# VHDCI_CON.net
KiCad netlist of a schematic drawn in Altium Designer
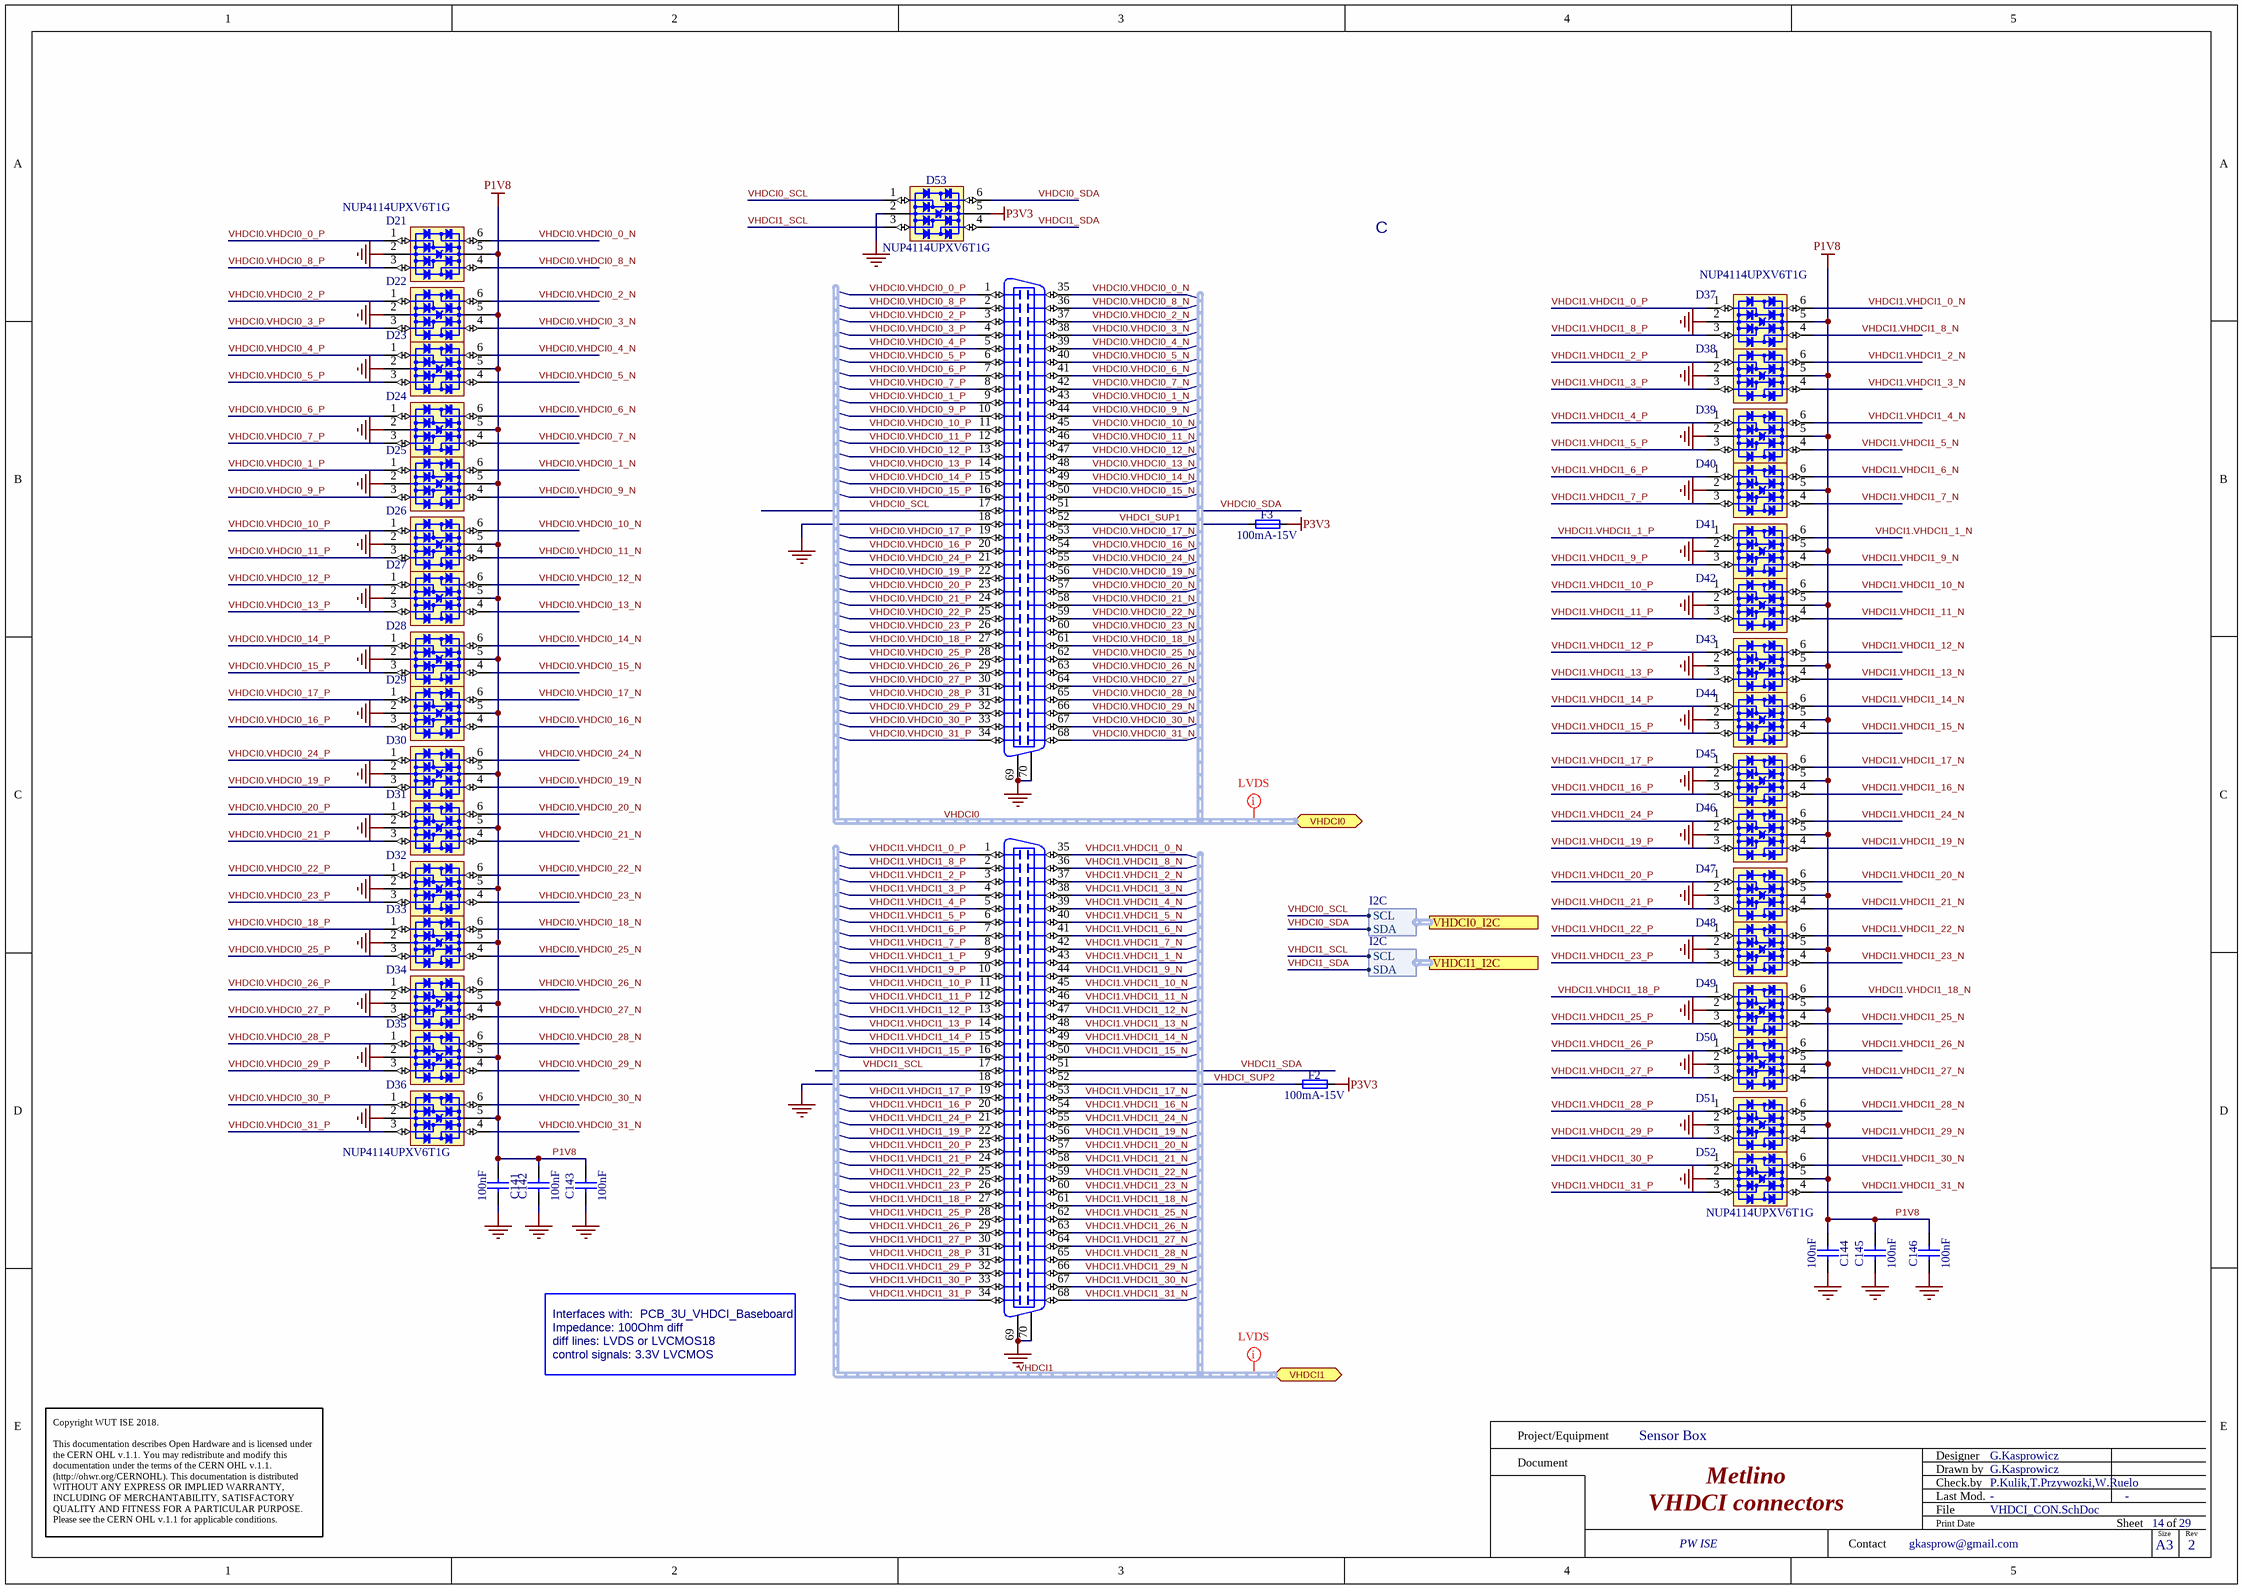
[diagram p0: VHDCI_CON.SchDoc]

(export (version "E")
  (design (tool "Eeschema 10.0.6"))
  (components
    (comp (ref "C141")
      (value "100nF")
      (footprint "CAPC0603X33N")
      (description "Non-polarised capacitor")
      (fields
        (field (name "MANUFACTURER PART NUMBER") "CC0201_100NF_6.3V_10%_X5R")
        (field (name "MANUFACTURER") "GENERIC")
        (field (name "AUTHOR") "CERN DEM JLC")
      )
      (libsource (lib "Capacitors") (part "Capacitor - non polarized"))
    )
    (comp (ref "C142")
      (value "100nF")
      (footprint "CAPC0603X33N")
      (description "Non-polarised capacitor")
      (fields
        (field (name "MANUFACTURER PART NUMBER") "CC0201_100NF_6.3V_10%_X5R")
        (field (name "MANUFACTURER") "GENERIC")
        (field (name "AUTHOR") "CERN DEM JLC")
      )
      (libsource (lib "Capacitors") (part "Capacitor - non polarized"))
    )
    (comp (ref "C143")
      (value "100nF")
      (footprint "CAPC0603X33N")
      (description "Non-polarised capacitor")
      (fields
        (field (name "MANUFACTURER PART NUMBER") "CC0201_100NF_6.3V_10%_X5R")
        (field (name "MANUFACTURER") "GENERIC")
        (field (name "AUTHOR") "CERN DEM JLC")
      )
      (libsource (lib "Capacitors") (part "Capacitor - non polarized"))
    )
    (comp (ref "C144")
      (value "100nF")
      (footprint "CAPC0603X33N")
      (description "Non-polarised capacitor")
      (fields
        (field (name "MANUFACTURER PART NUMBER") "CC0201_100NF_6.3V_10%_X5R")
        (field (name "MANUFACTURER") "GENERIC")
        (field (name "AUTHOR") "CERN DEM JLC")
      )
      (libsource (lib "Capacitors") (part "Capacitor - non polarized"))
    )
    (comp (ref "C145")
      (value "100nF")
      (footprint "CAPC0603X33N")
      (description "Non-polarised capacitor")
      (fields
        (field (name "MANUFACTURER PART NUMBER") "CC0201_100NF_6.3V_10%_X5R")
        (field (name "MANUFACTURER") "GENERIC")
        (field (name "AUTHOR") "CERN DEM JLC")
      )
      (libsource (lib "Capacitors") (part "Capacitor - non polarized"))
    )
    (comp (ref "C146")
      (value "100nF")
      (footprint "CAPC0603X33N")
      (description "Non-polarised capacitor")
      (fields
        (field (name "MANUFACTURER PART NUMBER") "CC0201_100NF_6.3V_10%_X5R")
        (field (name "MANUFACTURER") "GENERIC")
        (field (name "AUTHOR") "CERN DEM JLC")
      )
      (libsource (lib "Capacitors") (part "Capacitor - non polarized"))
    )
    (comp (ref "D21")
      (value "NUP4114UPXV6T1G")
      (footprint "SOTFL50P160X60-6N")
      (fields
        (field (name "MANUFACTURER") "ON SEMICONDUCTOR")
        (field (name "VOLTAGE") "5.5V")
        (field (name "AUTHOR") "CERN DEM JLC")
      )
      (libsource (lib "ICs And Semiconductors") (part "NUP4114"))
    )
    (comp (ref "D22")
      (value "NUP4114UPXV6T1G")
      (footprint "SOTFL50P160X60-6N")
      (fields
        (field (name "MANUFACTURER") "ON SEMICONDUCTOR")
        (field (name "VOLTAGE") "5.5V")
        (field (name "AUTHOR") "CERN DEM JLC")
      )
      (libsource (lib "ICs And Semiconductors") (part "NUP4114"))
    )
    (comp (ref "D23")
      (value "NUP4114UPXV6T1G")
      (footprint "SOTFL50P160X60-6N")
      (fields
        (field (name "MANUFACTURER") "ON SEMICONDUCTOR")
        (field (name "VOLTAGE") "5.5V")
        (field (name "AUTHOR") "CERN DEM JLC")
      )
      (libsource (lib "ICs And Semiconductors") (part "NUP4114"))
    )
    (comp (ref "D24")
      (value "NUP4114UPXV6T1G")
      (footprint "SOTFL50P160X60-6N")
      (fields
        (field (name "MANUFACTURER") "ON SEMICONDUCTOR")
        (field (name "VOLTAGE") "5.5V")
        (field (name "AUTHOR") "CERN DEM JLC")
      )
      (libsource (lib "ICs And Semiconductors") (part "NUP4114"))
    )
    (comp (ref "D25")
      (value "NUP4114UPXV6T1G")
      (footprint "SOTFL50P160X60-6N")
      (fields
        (field (name "MANUFACTURER") "ON SEMICONDUCTOR")
        (field (name "VOLTAGE") "5.5V")
        (field (name "AUTHOR") "CERN DEM JLC")
      )
      (libsource (lib "ICs And Semiconductors") (part "NUP4114"))
    )
    (comp (ref "D26")
      (value "NUP4114UPXV6T1G")
      (footprint "SOTFL50P160X60-6N")
      (fields
        (field (name "MANUFACTURER") "ON SEMICONDUCTOR")
        (field (name "VOLTAGE") "5.5V")
        (field (name "AUTHOR") "CERN DEM JLC")
      )
      (libsource (lib "ICs And Semiconductors") (part "NUP4114"))
    )
    (comp (ref "D27")
      (value "NUP4114UPXV6T1G")
      (footprint "SOTFL50P160X60-6N")
      (fields
        (field (name "MANUFACTURER") "ON SEMICONDUCTOR")
        (field (name "VOLTAGE") "5.5V")
        (field (name "AUTHOR") "CERN DEM JLC")
      )
      (libsource (lib "ICs And Semiconductors") (part "NUP4114"))
    )
    (comp (ref "D28")
      (value "NUP4114UPXV6T1G")
      (footprint "SOTFL50P160X60-6N")
      (fields
        (field (name "MANUFACTURER") "ON SEMICONDUCTOR")
        (field (name "VOLTAGE") "5.5V")
        (field (name "AUTHOR") "CERN DEM JLC")
      )
      (libsource (lib "ICs And Semiconductors") (part "NUP4114"))
    )
    (comp (ref "D29")
      (value "NUP4114UPXV6T1G")
      (footprint "SOTFL50P160X60-6N")
      (fields
        (field (name "MANUFACTURER") "ON SEMICONDUCTOR")
        (field (name "VOLTAGE") "5.5V")
        (field (name "AUTHOR") "CERN DEM JLC")
      )
      (libsource (lib "ICs And Semiconductors") (part "NUP4114"))
    )
    (comp (ref "D30")
      (value "NUP4114UPXV6T1G")
      (footprint "SOTFL50P160X60-6N")
      (fields
        (field (name "MANUFACTURER") "ON SEMICONDUCTOR")
        (field (name "VOLTAGE") "5.5V")
        (field (name "AUTHOR") "CERN DEM JLC")
      )
      (libsource (lib "ICs And Semiconductors") (part "NUP4114"))
    )
    (comp (ref "D31")
      (value "NUP4114UPXV6T1G")
      (footprint "SOTFL50P160X60-6N")
      (fields
        (field (name "MANUFACTURER") "ON SEMICONDUCTOR")
        (field (name "VOLTAGE") "5.5V")
        (field (name "AUTHOR") "CERN DEM JLC")
      )
      (libsource (lib "ICs And Semiconductors") (part "NUP4114"))
    )
    (comp (ref "D32")
      (value "NUP4114UPXV6T1G")
      (footprint "SOTFL50P160X60-6N")
      (fields
        (field (name "MANUFACTURER") "ON SEMICONDUCTOR")
        (field (name "VOLTAGE") "5.5V")
        (field (name "AUTHOR") "CERN DEM JLC")
      )
      (libsource (lib "ICs And Semiconductors") (part "NUP4114"))
    )
    (comp (ref "D33")
      (value "NUP4114UPXV6T1G")
      (footprint "SOTFL50P160X60-6N")
      (fields
        (field (name "MANUFACTURER") "ON SEMICONDUCTOR")
        (field (name "VOLTAGE") "5.5V")
        (field (name "AUTHOR") "CERN DEM JLC")
      )
      (libsource (lib "ICs And Semiconductors") (part "NUP4114"))
    )
    (comp (ref "D34")
      (value "NUP4114UPXV6T1G")
      (footprint "SOTFL50P160X60-6N")
      (fields
        (field (name "MANUFACTURER") "ON SEMICONDUCTOR")
        (field (name "VOLTAGE") "5.5V")
        (field (name "AUTHOR") "CERN DEM JLC")
      )
      (libsource (lib "ICs And Semiconductors") (part "NUP4114"))
    )
    (comp (ref "D35")
      (value "NUP4114UPXV6T1G")
      (footprint "SOTFL50P160X60-6N")
      (fields
        (field (name "MANUFACTURER") "ON SEMICONDUCTOR")
        (field (name "VOLTAGE") "5.5V")
        (field (name "AUTHOR") "CERN DEM JLC")
      )
      (libsource (lib "ICs And Semiconductors") (part "NUP4114"))
    )
    (comp (ref "D36")
      (value "NUP4114UPXV6T1G")
      (footprint "SOTFL50P160X60-6N")
      (fields
        (field (name "MANUFACTURER") "ON SEMICONDUCTOR")
        (field (name "VOLTAGE") "5.5V")
        (field (name "AUTHOR") "CERN DEM JLC")
      )
      (libsource (lib "ICs And Semiconductors") (part "NUP4114"))
    )
    (comp (ref "D37")
      (value "NUP4114UPXV6T1G")
      (footprint "SOTFL50P160X60-6N")
      (fields
        (field (name "MANUFACTURER") "ON SEMICONDUCTOR")
        (field (name "VOLTAGE") "5.5V")
        (field (name "AUTHOR") "CERN DEM JLC")
      )
      (libsource (lib "ICs And Semiconductors") (part "NUP4114"))
    )
    (comp (ref "D38")
      (value "NUP4114UPXV6T1G")
      (footprint "SOTFL50P160X60-6N")
      (fields
        (field (name "MANUFACTURER") "ON SEMICONDUCTOR")
        (field (name "VOLTAGE") "5.5V")
        (field (name "AUTHOR") "CERN DEM JLC")
      )
      (libsource (lib "ICs And Semiconductors") (part "NUP4114"))
    )
    (comp (ref "D39")
      (value "NUP4114UPXV6T1G")
      (footprint "SOTFL50P160X60-6N")
      (fields
        (field (name "MANUFACTURER") "ON SEMICONDUCTOR")
        (field (name "VOLTAGE") "5.5V")
        (field (name "AUTHOR") "CERN DEM JLC")
      )
      (libsource (lib "ICs And Semiconductors") (part "NUP4114"))
    )
    (comp (ref "D40")
      (value "NUP4114UPXV6T1G")
      (footprint "SOTFL50P160X60-6N")
      (fields
        (field (name "MANUFACTURER") "ON SEMICONDUCTOR")
        (field (name "VOLTAGE") "5.5V")
        (field (name "AUTHOR") "CERN DEM JLC")
      )
      (libsource (lib "ICs And Semiconductors") (part "NUP4114"))
    )
    (comp (ref "D41")
      (value "NUP4114UPXV6T1G")
      (footprint "SOTFL50P160X60-6N")
      (fields
        (field (name "MANUFACTURER") "ON SEMICONDUCTOR")
        (field (name "VOLTAGE") "5.5V")
        (field (name "AUTHOR") "CERN DEM JLC")
      )
      (libsource (lib "ICs And Semiconductors") (part "NUP4114"))
    )
    (comp (ref "D42")
      (value "NUP4114UPXV6T1G")
      (footprint "SOTFL50P160X60-6N")
      (fields
        (field (name "MANUFACTURER") "ON SEMICONDUCTOR")
        (field (name "VOLTAGE") "5.5V")
        (field (name "AUTHOR") "CERN DEM JLC")
      )
      (libsource (lib "ICs And Semiconductors") (part "NUP4114"))
    )
    (comp (ref "D43")
      (value "NUP4114UPXV6T1G")
      (footprint "SOTFL50P160X60-6N")
      (fields
        (field (name "MANUFACTURER") "ON SEMICONDUCTOR")
        (field (name "VOLTAGE") "5.5V")
        (field (name "AUTHOR") "CERN DEM JLC")
      )
      (libsource (lib "ICs And Semiconductors") (part "NUP4114"))
    )
    (comp (ref "D44")
      (value "NUP4114UPXV6T1G")
      (footprint "SOTFL50P160X60-6N")
      (fields
        (field (name "MANUFACTURER") "ON SEMICONDUCTOR")
        (field (name "VOLTAGE") "5.5V")
        (field (name "AUTHOR") "CERN DEM JLC")
      )
      (libsource (lib "ICs And Semiconductors") (part "NUP4114"))
    )
    (comp (ref "D45")
      (value "NUP4114UPXV6T1G")
      (footprint "SOTFL50P160X60-6N")
      (fields
        (field (name "MANUFACTURER") "ON SEMICONDUCTOR")
        (field (name "VOLTAGE") "5.5V")
        (field (name "AUTHOR") "CERN DEM JLC")
      )
      (libsource (lib "ICs And Semiconductors") (part "NUP4114"))
    )
    (comp (ref "D46")
      (value "NUP4114UPXV6T1G")
      (footprint "SOTFL50P160X60-6N")
      (fields
        (field (name "MANUFACTURER") "ON SEMICONDUCTOR")
        (field (name "VOLTAGE") "5.5V")
        (field (name "AUTHOR") "CERN DEM JLC")
      )
      (libsource (lib "ICs And Semiconductors") (part "NUP4114"))
    )
    (comp (ref "D47")
      (value "NUP4114UPXV6T1G")
      (footprint "SOTFL50P160X60-6N")
      (fields
        (field (name "MANUFACTURER") "ON SEMICONDUCTOR")
        (field (name "VOLTAGE") "5.5V")
        (field (name "AUTHOR") "CERN DEM JLC")
      )
      (libsource (lib "ICs And Semiconductors") (part "NUP4114"))
    )
    (comp (ref "D48")
      (value "NUP4114UPXV6T1G")
      (footprint "SOTFL50P160X60-6N")
      (fields
        (field (name "MANUFACTURER") "ON SEMICONDUCTOR")
        (field (name "VOLTAGE") "5.5V")
        (field (name "AUTHOR") "CERN DEM JLC")
      )
      (libsource (lib "ICs And Semiconductors") (part "NUP4114"))
    )
    (comp (ref "D49")
      (value "NUP4114UPXV6T1G")
      (footprint "SOTFL50P160X60-6N")
      (fields
        (field (name "MANUFACTURER") "ON SEMICONDUCTOR")
        (field (name "VOLTAGE") "5.5V")
        (field (name "AUTHOR") "CERN DEM JLC")
      )
      (libsource (lib "ICs And Semiconductors") (part "NUP4114"))
    )
    (comp (ref "D50")
      (value "NUP4114UPXV6T1G")
      (footprint "SOTFL50P160X60-6N")
      (fields
        (field (name "MANUFACTURER") "ON SEMICONDUCTOR")
        (field (name "VOLTAGE") "5.5V")
        (field (name "AUTHOR") "CERN DEM JLC")
      )
      (libsource (lib "ICs And Semiconductors") (part "NUP4114"))
    )
    (comp (ref "D51")
      (value "NUP4114UPXV6T1G")
      (footprint "SOTFL50P160X60-6N")
      (fields
        (field (name "MANUFACTURER") "ON SEMICONDUCTOR")
        (field (name "VOLTAGE") "5.5V")
        (field (name "AUTHOR") "CERN DEM JLC")
      )
      (libsource (lib "ICs And Semiconductors") (part "NUP4114"))
    )
    (comp (ref "D52")
      (value "NUP4114UPXV6T1G")
      (footprint "SOTFL50P160X60-6N")
      (fields
        (field (name "MANUFACTURER") "ON SEMICONDUCTOR")
        (field (name "VOLTAGE") "5.5V")
        (field (name "AUTHOR") "CERN DEM JLC")
      )
      (libsource (lib "ICs And Semiconductors") (part "NUP4114"))
    )
    (comp (ref "D53")
      (value "NUP4114UPXV6T1G")
      (footprint "SOTFL50P160X60-6N")
      (fields
        (field (name "MANUFACTURER") "ON SEMICONDUCTOR")
        (field (name "VOLTAGE") "5.5V")
        (field (name "AUTHOR") "CERN DEM JLC")
      )
      (libsource (lib "ICs And Semiconductors") (part "NUP4114"))
    )
    (comp (ref "F2")
      (value "100mA-15V")
      (footprint "FUSR_LITTELFUSE_0805L010")
      (description "Fuse")
      (fields
        (field (name "MANUFACTURER PART NUMBER") "0805L010YR")
        (field (name "MANUFACTURER") "LITTELFUSE")
        (field (name "AUTHOR") "CERN DEM JLC")
      )
      (libsource (lib "Eletro-mechanical") (part "Fuse"))
    )
    (comp (ref "F3")
      (value "100mA-15V")
      (footprint "FUSR_LITTELFUSE_0805L010")
      (description "Fuse")
      (fields
        (field (name "MANUFACTURER PART NUMBER") "0805L010YR")
        (field (name "MANUFACTURER") "LITTELFUSE")
        (field (name "AUTHOR") "CERN DEM JLC")
      )
      (libsource (lib "Eletro-mechanical") (part "Fuse"))
    )
    (comp (ref "J14")
      (value "VHDCI")
      (footprint "MOLEX_71430-0013")
      (description "Very High Density Cable Interconnect (VHDCI ) 68 Female")
      (fields
        (field (name "MANUFACTURER PART NUMBER") "71430-0013")
        (field (name "MANUFACTURER") "MOLEX")
        (field (name "AUTHOR") "CERN DEM JLC")
      )
      (libsource (lib "Connectors") (part "Connector VHDCI 68 Female"))
    )
    (comp (ref "J15")
      (value "VHDCI")
      (footprint "MOLEX_71430-0013")
      (description "Very High Density Cable Interconnect (VHDCI ) 68 Female")
      (fields
        (field (name "MANUFACTURER PART NUMBER") "71430-0013")
        (field (name "MANUFACTURER") "MOLEX")
        (field (name "AUTHOR") "CERN DEM JLC")
      )
      (libsource (lib "Connectors") (part "Connector VHDCI 68 Female"))
    )
  )
  (nets
    (net (code "4") (name "/VHDCI0.VHDCI0_0_N") (class "Default")
      (node (ref "D21") (pin "6") (pinfunction "I/O4_6") (pintype "bidirectional"))
      (node (ref "J14") (pin "35") (pinfunction "35_35") (pintype "bidirectional"))
    )
    (net (code "5") (name "/VHDCI0.VHDCI0_0_P") (class "Default")
      (node (ref "D21") (pin "1") (pinfunction "I/O1_1") (pintype "bidirectional"))
      (node (ref "J14") (pin "1") (pinfunction "1_1") (pintype "bidirectional"))
    )
    (net (code "6") (name "/VHDCI0.VHDCI0_1_N") (class "Default")
      (node (ref "D25") (pin "6") (pinfunction "I/O4_6") (pintype "bidirectional"))
      (node (ref "J14") (pin "43") (pinfunction "43_43") (pintype "bidirectional"))
    )
    (net (code "7") (name "/VHDCI0.VHDCI0_1_P") (class "Default")
      (node (ref "D25") (pin "1") (pinfunction "I/O1_1") (pintype "bidirectional"))
      (node (ref "J14") (pin "9") (pinfunction "9_9") (pintype "bidirectional"))
    )
    (net (code "8") (name "/VHDCI0.VHDCI0_2_N") (class "Default")
      (node (ref "D22") (pin "6") (pinfunction "I/O4_6") (pintype "bidirectional"))
      (node (ref "J14") (pin "37") (pinfunction "37_37") (pintype "bidirectional"))
    )
    (net (code "9") (name "/VHDCI0.VHDCI0_2_P") (class "Default")
      (node (ref "D22") (pin "1") (pinfunction "I/O1_1") (pintype "bidirectional"))
      (node (ref "J14") (pin "3") (pinfunction "3_3") (pintype "bidirectional"))
    )
    (net (code "10") (name "/VHDCI0.VHDCI0_3_N") (class "Default")
      (node (ref "D22") (pin "4") (pinfunction "I/O3_4") (pintype "bidirectional"))
      (node (ref "J14") (pin "38") (pinfunction "38_38") (pintype "bidirectional"))
    )
    (net (code "11") (name "/VHDCI0.VHDCI0_3_P") (class "Default")
      (node (ref "D22") (pin "3") (pinfunction "I/O2_3") (pintype "bidirectional"))
      (node (ref "J14") (pin "4") (pinfunction "4_4") (pintype "bidirectional"))
    )
    (net (code "12") (name "/VHDCI0.VHDCI0_4_N") (class "Default")
      (node (ref "D23") (pin "6") (pinfunction "I/O4_6") (pintype "bidirectional"))
      (node (ref "J14") (pin "39") (pinfunction "39_39") (pintype "bidirectional"))
    )
    (net (code "13") (name "/VHDCI0.VHDCI0_4_P") (class "Default")
      (node (ref "D23") (pin "1") (pinfunction "I/O1_1") (pintype "bidirectional"))
      (node (ref "J14") (pin "5") (pinfunction "5_5") (pintype "bidirectional"))
    )
    (net (code "14") (name "/VHDCI0.VHDCI0_5_N") (class "Default")
      (node (ref "D23") (pin "4") (pinfunction "I/O3_4") (pintype "bidirectional"))
      (node (ref "J14") (pin "40") (pinfunction "40_40") (pintype "bidirectional"))
    )
    (net (code "15") (name "/VHDCI0.VHDCI0_5_P") (class "Default")
      (node (ref "D23") (pin "3") (pinfunction "I/O2_3") (pintype "bidirectional"))
      (node (ref "J14") (pin "6") (pinfunction "6_6") (pintype "bidirectional"))
    )
    (net (code "16") (name "/VHDCI0.VHDCI0_6_N") (class "Default")
      (node (ref "D24") (pin "6") (pinfunction "I/O4_6") (pintype "bidirectional"))
      (node (ref "J14") (pin "41") (pinfunction "41_41") (pintype "bidirectional"))
    )
    (net (code "17") (name "/VHDCI0.VHDCI0_6_P") (class "Default")
      (node (ref "D24") (pin "1") (pinfunction "I/O1_1") (pintype "bidirectional"))
      (node (ref "J14") (pin "7") (pinfunction "7_7") (pintype "bidirectional"))
    )
    (net (code "18") (name "/VHDCI0.VHDCI0_7_N") (class "Default")
      (node (ref "D24") (pin "4") (pinfunction "I/O3_4") (pintype "bidirectional"))
      (node (ref "J14") (pin "42") (pinfunction "42_42") (pintype "bidirectional"))
    )
    (net (code "19") (name "/VHDCI0.VHDCI0_7_P") (class "Default")
      (node (ref "D24") (pin "3") (pinfunction "I/O2_3") (pintype "bidirectional"))
      (node (ref "J14") (pin "8") (pinfunction "8_8") (pintype "bidirectional"))
    )
    (net (code "20") (name "/VHDCI0.VHDCI0_8_N") (class "Default")
      (node (ref "D21") (pin "4") (pinfunction "I/O3_4") (pintype "bidirectional"))
      (node (ref "J14") (pin "36") (pinfunction "36_36") (pintype "bidirectional"))
    )
    (net (code "21") (name "/VHDCI0.VHDCI0_8_P") (class "Default")
      (node (ref "D21") (pin "3") (pinfunction "I/O2_3") (pintype "bidirectional"))
      (node (ref "J14") (pin "2") (pinfunction "2_2") (pintype "bidirectional"))
    )
    (net (code "22") (name "/VHDCI0.VHDCI0_9_N") (class "Default")
      (node (ref "D25") (pin "4") (pinfunction "I/O3_4") (pintype "bidirectional"))
      (node (ref "J14") (pin "44") (pinfunction "44_44") (pintype "bidirectional"))
    )
    (net (code "23") (name "/VHDCI0.VHDCI0_9_P") (class "Default")
      (node (ref "D25") (pin "3") (pinfunction "I/O2_3") (pintype "bidirectional"))
      (node (ref "J14") (pin "10") (pinfunction "10_10") (pintype "bidirectional"))
    )
    (net (code "24") (name "/VHDCI0.VHDCI0_10_N") (class "Default")
      (node (ref "D26") (pin "6") (pinfunction "I/O4_6") (pintype "bidirectional"))
      (node (ref "J14") (pin "45") (pinfunction "45_45") (pintype "bidirectional"))
    )
    (net (code "25") (name "/VHDCI0.VHDCI0_10_P") (class "Default")
      (node (ref "D26") (pin "1") (pinfunction "I/O1_1") (pintype "bidirectional"))
      (node (ref "J14") (pin "11") (pinfunction "11_11") (pintype "bidirectional"))
    )
    (net (code "26") (name "/VHDCI0.VHDCI0_11_N") (class "Default")
      (node (ref "D26") (pin "4") (pinfunction "I/O3_4") (pintype "bidirectional"))
      (node (ref "J14") (pin "46") (pinfunction "46_46") (pintype "bidirectional"))
    )
    (net (code "27") (name "/VHDCI0.VHDCI0_11_P") (class "Default")
      (node (ref "D26") (pin "3") (pinfunction "I/O2_3") (pintype "bidirectional"))
      (node (ref "J14") (pin "12") (pinfunction "12_12") (pintype "bidirectional"))
    )
    (net (code "28") (name "/VHDCI0.VHDCI0_12_N") (class "Default")
      (node (ref "D27") (pin "6") (pinfunction "I/O4_6") (pintype "bidirectional"))
      (node (ref "J14") (pin "47") (pinfunction "47_47") (pintype "bidirectional"))
    )
    (net (code "29") (name "/VHDCI0.VHDCI0_12_P") (class "Default")
      (node (ref "D27") (pin "1") (pinfunction "I/O1_1") (pintype "bidirectional"))
      (node (ref "J14") (pin "13") (pinfunction "13_13") (pintype "bidirectional"))
    )
    (net (code "30") (name "/VHDCI0.VHDCI0_13_N") (class "Default")
      (node (ref "D27") (pin "4") (pinfunction "I/O3_4") (pintype "bidirectional"))
      (node (ref "J14") (pin "48") (pinfunction "48_48") (pintype "bidirectional"))
    )
    (net (code "31") (name "/VHDCI0.VHDCI0_13_P") (class "Default")
      (node (ref "D27") (pin "3") (pinfunction "I/O2_3") (pintype "bidirectional"))
      (node (ref "J14") (pin "14") (pinfunction "14_14") (pintype "bidirectional"))
    )
    (net (code "32") (name "/VHDCI0.VHDCI0_14_N") (class "Default")
      (node (ref "D28") (pin "6") (pinfunction "I/O4_6") (pintype "bidirectional"))
      (node (ref "J14") (pin "49") (pinfunction "49_49") (pintype "bidirectional"))
    )
    (net (code "33") (name "/VHDCI0.VHDCI0_14_P") (class "Default")
      (node (ref "D28") (pin "1") (pinfunction "I/O1_1") (pintype "bidirectional"))
      (node (ref "J14") (pin "15") (pinfunction "15_15") (pintype "bidirectional"))
    )
    (net (code "34") (name "/VHDCI0.VHDCI0_15_N") (class "Default")
      (node (ref "D28") (pin "4") (pinfunction "I/O3_4") (pintype "bidirectional"))
      (node (ref "J14") (pin "50") (pinfunction "50_50") (pintype "bidirectional"))
    )
    (net (code "35") (name "/VHDCI0.VHDCI0_15_P") (class "Default")
      (node (ref "D28") (pin "3") (pinfunction "I/O2_3") (pintype "bidirectional"))
      (node (ref "J14") (pin "16") (pinfunction "16_16") (pintype "bidirectional"))
    )
    (net (code "36") (name "/VHDCI0.VHDCI0_16_N") (class "Default")
      (node (ref "D29") (pin "4") (pinfunction "I/O3_4") (pintype "bidirectional"))
      (node (ref "J14") (pin "54") (pinfunction "54_54") (pintype "bidirectional"))
    )
    (net (code "37") (name "/VHDCI0.VHDCI0_16_P") (class "Default")
      (node (ref "D29") (pin "3") (pinfunction "I/O2_3") (pintype "bidirectional"))
      (node (ref "J14") (pin "20") (pinfunction "20_20") (pintype "bidirectional"))
    )
    (net (code "38") (name "/VHDCI0.VHDCI0_17_N") (class "Default")
      (node (ref "D29") (pin "6") (pinfunction "I/O4_6") (pintype "bidirectional"))
      (node (ref "J14") (pin "53") (pinfunction "53_53") (pintype "bidirectional"))
    )
    (net (code "39") (name "/VHDCI0.VHDCI0_17_P") (class "Default")
      (node (ref "D29") (pin "1") (pinfunction "I/O1_1") (pintype "bidirectional"))
      (node (ref "J14") (pin "19") (pinfunction "19_19") (pintype "bidirectional"))
    )
    (net (code "40") (name "/VHDCI0.VHDCI0_18_N") (class "Default")
      (node (ref "D33") (pin "6") (pinfunction "I/O4_6") (pintype "bidirectional"))
      (node (ref "J14") (pin "61") (pinfunction "61_61") (pintype "bidirectional"))
    )
    (net (code "41") (name "/VHDCI0.VHDCI0_18_P") (class "Default")
      (node (ref "D33") (pin "1") (pinfunction "I/O1_1") (pintype "bidirectional"))
      (node (ref "J14") (pin "27") (pinfunction "27_27") (pintype "bidirectional"))
    )
    (net (code "42") (name "/VHDCI0.VHDCI0_19_N") (class "Default")
      (node (ref "D30") (pin "4") (pinfunction "I/O3_4") (pintype "bidirectional"))
      (node (ref "J14") (pin "56") (pinfunction "56_56") (pintype "bidirectional"))
    )
    (net (code "43") (name "/VHDCI0.VHDCI0_19_P") (class "Default")
      (node (ref "D30") (pin "3") (pinfunction "I/O2_3") (pintype "bidirectional"))
      (node (ref "J14") (pin "22") (pinfunction "22_22") (pintype "bidirectional"))
    )
    (net (code "44") (name "/VHDCI0.VHDCI0_20_N") (class "Default")
      (node (ref "D31") (pin "6") (pinfunction "I/O4_6") (pintype "bidirectional"))
      (node (ref "J14") (pin "57") (pinfunction "57_57") (pintype "bidirectional"))
    )
    (net (code "45") (name "/VHDCI0.VHDCI0_20_P") (class "Default")
      (node (ref "D31") (pin "1") (pinfunction "I/O1_1") (pintype "bidirectional"))
      (node (ref "J14") (pin "23") (pinfunction "23_23") (pintype "bidirectional"))
    )
    (net (code "46") (name "/VHDCI0.VHDCI0_21_N") (class "Default")
      (node (ref "D31") (pin "4") (pinfunction "I/O3_4") (pintype "bidirectional"))
      (node (ref "J14") (pin "58") (pinfunction "58_58") (pintype "bidirectional"))
    )
    (net (code "47") (name "/VHDCI0.VHDCI0_21_P") (class "Default")
      (node (ref "D31") (pin "3") (pinfunction "I/O2_3") (pintype "bidirectional"))
      (node (ref "J14") (pin "24") (pinfunction "24_24") (pintype "bidirectional"))
    )
    (net (code "48") (name "/VHDCI0.VHDCI0_22_N") (class "Default")
      (node (ref "D32") (pin "6") (pinfunction "I/O4_6") (pintype "bidirectional"))
      (node (ref "J14") (pin "59") (pinfunction "59_59") (pintype "bidirectional"))
    )
    (net (code "49") (name "/VHDCI0.VHDCI0_22_P") (class "Default")
      (node (ref "D32") (pin "1") (pinfunction "I/O1_1") (pintype "bidirectional"))
      (node (ref "J14") (pin "25") (pinfunction "25_25") (pintype "bidirectional"))
    )
    (net (code "50") (name "/VHDCI0.VHDCI0_23_N") (class "Default")
      (node (ref "D32") (pin "4") (pinfunction "I/O3_4") (pintype "bidirectional"))
      (node (ref "J14") (pin "60") (pinfunction "60_60") (pintype "bidirectional"))
    )
    (net (code "51") (name "/VHDCI0.VHDCI0_23_P") (class "Default")
      (node (ref "D32") (pin "3") (pinfunction "I/O2_3") (pintype "bidirectional"))
      (node (ref "J14") (pin "26") (pinfunction "26_26") (pintype "bidirectional"))
    )
    (net (code "52") (name "/VHDCI0.VHDCI0_24_N") (class "Default")
      (node (ref "D30") (pin "6") (pinfunction "I/O4_6") (pintype "bidirectional"))
      (node (ref "J14") (pin "55") (pinfunction "55_55") (pintype "bidirectional"))
    )
    (net (code "53") (name "/VHDCI0.VHDCI0_24_P") (class "Default")
      (node (ref "D30") (pin "1") (pinfunction "I/O1_1") (pintype "bidirectional"))
      (node (ref "J14") (pin "21") (pinfunction "21_21") (pintype "bidirectional"))
    )
    (net (code "54") (name "/VHDCI0.VHDCI0_25_N") (class "Default")
      (node (ref "D33") (pin "4") (pinfunction "I/O3_4") (pintype "bidirectional"))
      (node (ref "J14") (pin "62") (pinfunction "62_62") (pintype "bidirectional"))
    )
    (net (code "55") (name "/VHDCI0.VHDCI0_25_P") (class "Default")
      (node (ref "D33") (pin "3") (pinfunction "I/O2_3") (pintype "bidirectional"))
      (node (ref "J14") (pin "28") (pinfunction "28_28") (pintype "bidirectional"))
    )
    (net (code "56") (name "/VHDCI0.VHDCI0_26_N") (class "Default")
      (node (ref "D34") (pin "6") (pinfunction "I/O4_6") (pintype "bidirectional"))
      (node (ref "J14") (pin "63") (pinfunction "63_63") (pintype "bidirectional"))
    )
    (net (code "57") (name "/VHDCI0.VHDCI0_26_P") (class "Default")
      (node (ref "D34") (pin "1") (pinfunction "I/O1_1") (pintype "bidirectional"))
      (node (ref "J14") (pin "29") (pinfunction "29_29") (pintype "bidirectional"))
    )
    (net (code "58") (name "/VHDCI0.VHDCI0_27_N") (class "Default")
      (node (ref "D34") (pin "4") (pinfunction "I/O3_4") (pintype "bidirectional"))
      (node (ref "J14") (pin "64") (pinfunction "64_64") (pintype "bidirectional"))
    )
    (net (code "59") (name "/VHDCI0.VHDCI0_27_P") (class "Default")
      (node (ref "D34") (pin "3") (pinfunction "I/O2_3") (pintype "bidirectional"))
      (node (ref "J14") (pin "30") (pinfunction "30_30") (pintype "bidirectional"))
    )
    (net (code "60") (name "/VHDCI0.VHDCI0_28_N") (class "Default")
      (node (ref "D35") (pin "6") (pinfunction "I/O4_6") (pintype "bidirectional"))
      (node (ref "J14") (pin "65") (pinfunction "65_65") (pintype "bidirectional"))
    )
    (net (code "61") (name "/VHDCI0.VHDCI0_28_P") (class "Default")
      (node (ref "D35") (pin "1") (pinfunction "I/O1_1") (pintype "bidirectional"))
      (node (ref "J14") (pin "31") (pinfunction "31_31") (pintype "bidirectional"))
    )
    (net (code "62") (name "/VHDCI0.VHDCI0_29_N") (class "Default")
      (node (ref "D35") (pin "4") (pinfunction "I/O3_4") (pintype "bidirectional"))
      (node (ref "J14") (pin "66") (pinfunction "66_66") (pintype "bidirectional"))
    )
    (net (code "63") (name "/VHDCI0.VHDCI0_29_P") (class "Default")
      (node (ref "D35") (pin "3") (pinfunction "I/O2_3") (pintype "bidirectional"))
      (node (ref "J14") (pin "32") (pinfunction "32_32") (pintype "bidirectional"))
    )
    (net (code "64") (name "/VHDCI0.VHDCI0_30_N") (class "Default")
      (node (ref "D36") (pin "6") (pinfunction "I/O4_6") (pintype "bidirectional"))
      (node (ref "J14") (pin "67") (pinfunction "67_67") (pintype "bidirectional"))
    )
    (net (code "65") (name "/VHDCI0.VHDCI0_30_P") (class "Default")
      (node (ref "D36") (pin "1") (pinfunction "I/O1_1") (pintype "bidirectional"))
      (node (ref "J14") (pin "33") (pinfunction "33_33") (pintype "bidirectional"))
    )
    (net (code "66") (name "/VHDCI0.VHDCI0_31_N") (class "Default")
      (node (ref "D36") (pin "4") (pinfunction "I/O3_4") (pintype "bidirectional"))
      (node (ref "J14") (pin "68") (pinfunction "68_68") (pintype "bidirectional"))
    )
    (net (code "67") (name "/VHDCI0.VHDCI0_31_P") (class "Default")
      (node (ref "D36") (pin "3") (pinfunction "I/O2_3") (pintype "bidirectional"))
      (node (ref "J14") (pin "34") (pinfunction "34_34") (pintype "bidirectional"))
    )
    (net (code "68") (name "/VHDCI0_SCL") (class "Default")
      (node (ref "D53") (pin "1") (pinfunction "I/O1_1") (pintype "bidirectional"))
      (node (ref "J14") (pin "17") (pinfunction "17_17") (pintype "bidirectional"))
    )
    (net (code "69") (name "/VHDCI0_SDA") (class "Default")
      (node (ref "D53") (pin "6") (pinfunction "I/O4_6") (pintype "bidirectional"))
      (node (ref "J14") (pin "51") (pinfunction "51_51") (pintype "bidirectional"))
    )
    (net (code "70") (name "/VHDCI1.VHDCI1_0_N") (class "Default")
      (node (ref "D37") (pin "6") (pinfunction "I/O4_6") (pintype "bidirectional"))
      (node (ref "J15") (pin "35") (pinfunction "35_35") (pintype "bidirectional"))
    )
    (net (code "71") (name "/VHDCI1.VHDCI1_0_P") (class "Default")
      (node (ref "D37") (pin "1") (pinfunction "I/O1_1") (pintype "bidirectional"))
      (node (ref "J15") (pin "1") (pinfunction "1_1") (pintype "bidirectional"))
    )
    (net (code "72") (name "/VHDCI1.VHDCI1_1_N") (class "Default")
      (node (ref "D41") (pin "6") (pinfunction "I/O4_6") (pintype "bidirectional"))
      (node (ref "J15") (pin "43") (pinfunction "43_43") (pintype "bidirectional"))
    )
    (net (code "73") (name "/VHDCI1.VHDCI1_1_P") (class "Default")
      (node (ref "D41") (pin "1") (pinfunction "I/O1_1") (pintype "bidirectional"))
      (node (ref "J15") (pin "9") (pinfunction "9_9") (pintype "bidirectional"))
    )
    (net (code "74") (name "/VHDCI1.VHDCI1_2_N") (class "Default")
      (node (ref "D38") (pin "6") (pinfunction "I/O4_6") (pintype "bidirectional"))
      (node (ref "J15") (pin "37") (pinfunction "37_37") (pintype "bidirectional"))
    )
    (net (code "75") (name "/VHDCI1.VHDCI1_2_P") (class "Default")
      (node (ref "D38") (pin "1") (pinfunction "I/O1_1") (pintype "bidirectional"))
      (node (ref "J15") (pin "3") (pinfunction "3_3") (pintype "bidirectional"))
    )
    (net (code "76") (name "/VHDCI1.VHDCI1_3_N") (class "Default")
      (node (ref "D38") (pin "4") (pinfunction "I/O3_4") (pintype "bidirectional"))
      (node (ref "J15") (pin "38") (pinfunction "38_38") (pintype "bidirectional"))
    )
    (net (code "77") (name "/VHDCI1.VHDCI1_3_P") (class "Default")
      (node (ref "D38") (pin "3") (pinfunction "I/O2_3") (pintype "bidirectional"))
      (node (ref "J15") (pin "4") (pinfunction "4_4") (pintype "bidirectional"))
    )
    (net (code "78") (name "/VHDCI1.VHDCI1_4_N") (class "Default")
      (node (ref "D39") (pin "6") (pinfunction "I/O4_6") (pintype "bidirectional"))
      (node (ref "J15") (pin "39") (pinfunction "39_39") (pintype "bidirectional"))
    )
    (net (code "79") (name "/VHDCI1.VHDCI1_4_P") (class "Default")
      (node (ref "D39") (pin "1") (pinfunction "I/O1_1") (pintype "bidirectional"))
      (node (ref "J15") (pin "5") (pinfunction "5_5") (pintype "bidirectional"))
    )
    (net (code "80") (name "/VHDCI1.VHDCI1_5_N") (class "Default")
      (node (ref "D39") (pin "4") (pinfunction "I/O3_4") (pintype "bidirectional"))
      (node (ref "J15") (pin "40") (pinfunction "40_40") (pintype "bidirectional"))
    )
    (net (code "81") (name "/VHDCI1.VHDCI1_5_P") (class "Default")
      (node (ref "D39") (pin "3") (pinfunction "I/O2_3") (pintype "bidirectional"))
      (node (ref "J15") (pin "6") (pinfunction "6_6") (pintype "bidirectional"))
    )
    (net (code "82") (name "/VHDCI1.VHDCI1_6_N") (class "Default")
      (node (ref "D40") (pin "6") (pinfunction "I/O4_6") (pintype "bidirectional"))
      (node (ref "J15") (pin "41") (pinfunction "41_41") (pintype "bidirectional"))
    )
    (net (code "83") (name "/VHDCI1.VHDCI1_6_P") (class "Default")
      (node (ref "D40") (pin "1") (pinfunction "I/O1_1") (pintype "bidirectional"))
      (node (ref "J15") (pin "7") (pinfunction "7_7") (pintype "bidirectional"))
    )
    (net (code "84") (name "/VHDCI1.VHDCI1_7_N") (class "Default")
      (node (ref "D40") (pin "4") (pinfunction "I/O3_4") (pintype "bidirectional"))
      (node (ref "J15") (pin "42") (pinfunction "42_42") (pintype "bidirectional"))
    )
    (net (code "85") (name "/VHDCI1.VHDCI1_7_P") (class "Default")
      (node (ref "D40") (pin "3") (pinfunction "I/O2_3") (pintype "bidirectional"))
      (node (ref "J15") (pin "8") (pinfunction "8_8") (pintype "bidirectional"))
    )
    (net (code "86") (name "/VHDCI1.VHDCI1_8_N") (class "Default")
      (node (ref "D37") (pin "4") (pinfunction "I/O3_4") (pintype "bidirectional"))
      (node (ref "J15") (pin "36") (pinfunction "36_36") (pintype "bidirectional"))
    )
    (net (code "87") (name "/VHDCI1.VHDCI1_8_P") (class "Default")
      (node (ref "D37") (pin "3") (pinfunction "I/O2_3") (pintype "bidirectional"))
      (node (ref "J15") (pin "2") (pinfunction "2_2") (pintype "bidirectional"))
    )
    (net (code "88") (name "/VHDCI1.VHDCI1_9_N") (class "Default")
      (node (ref "D41") (pin "4") (pinfunction "I/O3_4") (pintype "bidirectional"))
      (node (ref "J15") (pin "44") (pinfunction "44_44") (pintype "bidirectional"))
    )
    (net (code "89") (name "/VHDCI1.VHDCI1_9_P") (class "Default")
      (node (ref "D41") (pin "3") (pinfunction "I/O2_3") (pintype "bidirectional"))
      (node (ref "J15") (pin "10") (pinfunction "10_10") (pintype "bidirectional"))
    )
    (net (code "90") (name "/VHDCI1.VHDCI1_10_N") (class "Default")
      (node (ref "D42") (pin "6") (pinfunction "I/O4_6") (pintype "bidirectional"))
      (node (ref "J15") (pin "45") (pinfunction "45_45") (pintype "bidirectional"))
    )
    (net (code "91") (name "/VHDCI1.VHDCI1_10_P") (class "Default")
      (node (ref "D42") (pin "1") (pinfunction "I/O1_1") (pintype "bidirectional"))
      (node (ref "J15") (pin "11") (pinfunction "11_11") (pintype "bidirectional"))
    )
    (net (code "92") (name "/VHDCI1.VHDCI1_11_N") (class "Default")
      (node (ref "D42") (pin "4") (pinfunction "I/O3_4") (pintype "bidirectional"))
      (node (ref "J15") (pin "46") (pinfunction "46_46") (pintype "bidirectional"))
    )
    (net (code "93") (name "/VHDCI1.VHDCI1_11_P") (class "Default")
      (node (ref "D42") (pin "3") (pinfunction "I/O2_3") (pintype "bidirectional"))
      (node (ref "J15") (pin "12") (pinfunction "12_12") (pintype "bidirectional"))
    )
    (net (code "94") (name "/VHDCI1.VHDCI1_12_N") (class "Default")
      (node (ref "D43") (pin "6") (pinfunction "I/O4_6") (pintype "bidirectional"))
      (node (ref "J15") (pin "47") (pinfunction "47_47") (pintype "bidirectional"))
    )
    (net (code "95") (name "/VHDCI1.VHDCI1_12_P") (class "Default")
      (node (ref "D43") (pin "1") (pinfunction "I/O1_1") (pintype "bidirectional"))
      (node (ref "J15") (pin "13") (pinfunction "13_13") (pintype "bidirectional"))
    )
    (net (code "96") (name "/VHDCI1.VHDCI1_13_N") (class "Default")
      (node (ref "D43") (pin "4") (pinfunction "I/O3_4") (pintype "bidirectional"))
      (node (ref "J15") (pin "48") (pinfunction "48_48") (pintype "bidirectional"))
    )
    (net (code "97") (name "/VHDCI1.VHDCI1_13_P") (class "Default")
      (node (ref "D43") (pin "3") (pinfunction "I/O2_3") (pintype "bidirectional"))
      (node (ref "J15") (pin "14") (pinfunction "14_14") (pintype "bidirectional"))
    )
    (net (code "98") (name "/VHDCI1.VHDCI1_14_N") (class "Default")
      (node (ref "D44") (pin "6") (pinfunction "I/O4_6") (pintype "bidirectional"))
      (node (ref "J15") (pin "49") (pinfunction "49_49") (pintype "bidirectional"))
    )
    (net (code "99") (name "/VHDCI1.VHDCI1_14_P") (class "Default")
      (node (ref "D44") (pin "1") (pinfunction "I/O1_1") (pintype "bidirectional"))
      (node (ref "J15") (pin "15") (pinfunction "15_15") (pintype "bidirectional"))
    )
    (net (code "100") (name "/VHDCI1.VHDCI1_15_N") (class "Default")
      (node (ref "D44") (pin "4") (pinfunction "I/O3_4") (pintype "bidirectional"))
      (node (ref "J15") (pin "50") (pinfunction "50_50") (pintype "bidirectional"))
    )
    (net (code "101") (name "/VHDCI1.VHDCI1_15_P") (class "Default")
      (node (ref "D44") (pin "3") (pinfunction "I/O2_3") (pintype "bidirectional"))
      (node (ref "J15") (pin "16") (pinfunction "16_16") (pintype "bidirectional"))
    )
    (net (code "102") (name "/VHDCI1.VHDCI1_16_N") (class "Default")
      (node (ref "D45") (pin "4") (pinfunction "I/O3_4") (pintype "bidirectional"))
      (node (ref "J15") (pin "54") (pinfunction "54_54") (pintype "bidirectional"))
    )
    (net (code "103") (name "/VHDCI1.VHDCI1_16_P") (class "Default")
      (node (ref "D45") (pin "3") (pinfunction "I/O2_3") (pintype "bidirectional"))
      (node (ref "J15") (pin "20") (pinfunction "20_20") (pintype "bidirectional"))
    )
    (net (code "104") (name "/VHDCI1.VHDCI1_17_N") (class "Default")
      (node (ref "D45") (pin "6") (pinfunction "I/O4_6") (pintype "bidirectional"))
      (node (ref "J15") (pin "53") (pinfunction "53_53") (pintype "bidirectional"))
    )
    (net (code "105") (name "/VHDCI1.VHDCI1_17_P") (class "Default")
      (node (ref "D45") (pin "1") (pinfunction "I/O1_1") (pintype "bidirectional"))
      (node (ref "J15") (pin "19") (pinfunction "19_19") (pintype "bidirectional"))
    )
    (net (code "106") (name "/VHDCI1.VHDCI1_18_N") (class "Default")
      (node (ref "D49") (pin "6") (pinfunction "I/O4_6") (pintype "bidirectional"))
      (node (ref "J15") (pin "61") (pinfunction "61_61") (pintype "bidirectional"))
    )
    (net (code "107") (name "/VHDCI1.VHDCI1_18_P") (class "Default")
      (node (ref "D49") (pin "1") (pinfunction "I/O1_1") (pintype "bidirectional"))
      (node (ref "J15") (pin "27") (pinfunction "27_27") (pintype "bidirectional"))
    )
    (net (code "108") (name "/VHDCI1.VHDCI1_19_N") (class "Default")
      (node (ref "D46") (pin "4") (pinfunction "I/O3_4") (pintype "bidirectional"))
      (node (ref "J15") (pin "56") (pinfunction "56_56") (pintype "bidirectional"))
    )
    (net (code "109") (name "/VHDCI1.VHDCI1_19_P") (class "Default")
      (node (ref "D46") (pin "3") (pinfunction "I/O2_3") (pintype "bidirectional"))
      (node (ref "J15") (pin "22") (pinfunction "22_22") (pintype "bidirectional"))
    )
    (net (code "110") (name "/VHDCI1.VHDCI1_20_N") (class "Default")
      (node (ref "D47") (pin "6") (pinfunction "I/O4_6") (pintype "bidirectional"))
      (node (ref "J15") (pin "57") (pinfunction "57_57") (pintype "bidirectional"))
    )
    (net (code "111") (name "/VHDCI1.VHDCI1_20_P") (class "Default")
      (node (ref "D47") (pin "1") (pinfunction "I/O1_1") (pintype "bidirectional"))
      (node (ref "J15") (pin "23") (pinfunction "23_23") (pintype "bidirectional"))
    )
    (net (code "112") (name "/VHDCI1.VHDCI1_21_N") (class "Default")
      (node (ref "D47") (pin "4") (pinfunction "I/O3_4") (pintype "bidirectional"))
      (node (ref "J15") (pin "58") (pinfunction "58_58") (pintype "bidirectional"))
    )
    (net (code "113") (name "/VHDCI1.VHDCI1_21_P") (class "Default")
      (node (ref "D47") (pin "3") (pinfunction "I/O2_3") (pintype "bidirectional"))
      (node (ref "J15") (pin "24") (pinfunction "24_24") (pintype "bidirectional"))
    )
    (net (code "114") (name "/VHDCI1.VHDCI1_22_N") (class "Default")
      (node (ref "D48") (pin "6") (pinfunction "I/O4_6") (pintype "bidirectional"))
      (node (ref "J15") (pin "59") (pinfunction "59_59") (pintype "bidirectional"))
    )
    (net (code "115") (name "/VHDCI1.VHDCI1_22_P") (class "Default")
      (node (ref "D48") (pin "1") (pinfunction "I/O1_1") (pintype "bidirectional"))
      (node (ref "J15") (pin "25") (pinfunction "25_25") (pintype "bidirectional"))
    )
    (net (code "116") (name "/VHDCI1.VHDCI1_23_N") (class "Default")
      (node (ref "D48") (pin "4") (pinfunction "I/O3_4") (pintype "bidirectional"))
      (node (ref "J15") (pin "60") (pinfunction "60_60") (pintype "bidirectional"))
    )
    (net (code "117") (name "/VHDCI1.VHDCI1_23_P") (class "Default")
      (node (ref "D48") (pin "3") (pinfunction "I/O2_3") (pintype "bidirectional"))
      (node (ref "J15") (pin "26") (pinfunction "26_26") (pintype "bidirectional"))
    )
    (net (code "118") (name "/VHDCI1.VHDCI1_24_N") (class "Default")
      (node (ref "D46") (pin "6") (pinfunction "I/O4_6") (pintype "bidirectional"))
      (node (ref "J15") (pin "55") (pinfunction "55_55") (pintype "bidirectional"))
    )
    (net (code "119") (name "/VHDCI1.VHDCI1_24_P") (class "Default")
      (node (ref "D46") (pin "1") (pinfunction "I/O1_1") (pintype "bidirectional"))
      (node (ref "J15") (pin "21") (pinfunction "21_21") (pintype "bidirectional"))
    )
    (net (code "120") (name "/VHDCI1.VHDCI1_25_N") (class "Default")
      (node (ref "D49") (pin "4") (pinfunction "I/O3_4") (pintype "bidirectional"))
      (node (ref "J15") (pin "62") (pinfunction "62_62") (pintype "bidirectional"))
    )
    (net (code "121") (name "/VHDCI1.VHDCI1_25_P") (class "Default")
      (node (ref "D49") (pin "3") (pinfunction "I/O2_3") (pintype "bidirectional"))
      (node (ref "J15") (pin "28") (pinfunction "28_28") (pintype "bidirectional"))
    )
    (net (code "122") (name "/VHDCI1.VHDCI1_26_N") (class "Default")
      (node (ref "D50") (pin "6") (pinfunction "I/O4_6") (pintype "bidirectional"))
      (node (ref "J15") (pin "63") (pinfunction "63_63") (pintype "bidirectional"))
    )
    (net (code "123") (name "/VHDCI1.VHDCI1_26_P") (class "Default")
      (node (ref "D50") (pin "1") (pinfunction "I/O1_1") (pintype "bidirectional"))
      (node (ref "J15") (pin "29") (pinfunction "29_29") (pintype "bidirectional"))
    )
    (net (code "124") (name "/VHDCI1.VHDCI1_27_N") (class "Default")
      (node (ref "D50") (pin "4") (pinfunction "I/O3_4") (pintype "bidirectional"))
      (node (ref "J15") (pin "64") (pinfunction "64_64") (pintype "bidirectional"))
    )
    (net (code "125") (name "/VHDCI1.VHDCI1_27_P") (class "Default")
      (node (ref "D50") (pin "3") (pinfunction "I/O2_3") (pintype "bidirectional"))
      (node (ref "J15") (pin "30") (pinfunction "30_30") (pintype "bidirectional"))
    )
    (net (code "126") (name "/VHDCI1.VHDCI1_28_N") (class "Default")
      (node (ref "D51") (pin "6") (pinfunction "I/O4_6") (pintype "bidirectional"))
      (node (ref "J15") (pin "65") (pinfunction "65_65") (pintype "bidirectional"))
    )
    (net (code "127") (name "/VHDCI1.VHDCI1_28_P") (class "Default")
      (node (ref "D51") (pin "1") (pinfunction "I/O1_1") (pintype "bidirectional"))
      (node (ref "J15") (pin "31") (pinfunction "31_31") (pintype "bidirectional"))
    )
    (net (code "128") (name "/VHDCI1.VHDCI1_29_N") (class "Default")
      (node (ref "D51") (pin "4") (pinfunction "I/O3_4") (pintype "bidirectional"))
      (node (ref "J15") (pin "66") (pinfunction "66_66") (pintype "bidirectional"))
    )
    (net (code "129") (name "/VHDCI1.VHDCI1_29_P") (class "Default")
      (node (ref "D51") (pin "3") (pinfunction "I/O2_3") (pintype "bidirectional"))
      (node (ref "J15") (pin "32") (pinfunction "32_32") (pintype "bidirectional"))
    )
    (net (code "130") (name "/VHDCI1.VHDCI1_30_N") (class "Default")
      (node (ref "D52") (pin "6") (pinfunction "I/O4_6") (pintype "bidirectional"))
      (node (ref "J15") (pin "67") (pinfunction "67_67") (pintype "bidirectional"))
    )
    (net (code "131") (name "/VHDCI1.VHDCI1_30_P") (class "Default")
      (node (ref "D52") (pin "1") (pinfunction "I/O1_1") (pintype "bidirectional"))
      (node (ref "J15") (pin "33") (pinfunction "33_33") (pintype "bidirectional"))
    )
    (net (code "132") (name "/VHDCI1.VHDCI1_31_N") (class "Default")
      (node (ref "D52") (pin "4") (pinfunction "I/O3_4") (pintype "bidirectional"))
      (node (ref "J15") (pin "68") (pinfunction "68_68") (pintype "bidirectional"))
    )
    (net (code "133") (name "/VHDCI1.VHDCI1_31_P") (class "Default")
      (node (ref "D52") (pin "3") (pinfunction "I/O2_3") (pintype "bidirectional"))
      (node (ref "J15") (pin "34") (pinfunction "34_34") (pintype "bidirectional"))
    )
    (net (code "134") (name "/VHDCI1_SCL") (class "Default")
      (node (ref "D53") (pin "3") (pinfunction "I/O2_3") (pintype "bidirectional"))
      (node (ref "J15") (pin "17") (pinfunction "17_17") (pintype "bidirectional"))
    )
    (net (code "135") (name "/VHDCI1_SDA") (class "Default")
      (node (ref "D53") (pin "4") (pinfunction "I/O3_4") (pintype "bidirectional"))
      (node (ref "J15") (pin "51") (pinfunction "51_51") (pintype "bidirectional"))
    )
    (net (code "136") (name "/VHDCI_SUP1") (class "Default")
      (node (ref "F3") (pin "1") (pinfunction "1_1") (pintype "passive"))
      (node (ref "J14") (pin "52") (pinfunction "52_52") (pintype "bidirectional"))
    )
    (net (code "137") (name "/VHDCI_SUP2") (class "Default")
      (node (ref "F2") (pin "1") (pinfunction "1_1") (pintype "passive"))
      (node (ref "J15") (pin "52") (pinfunction "52_52") (pintype "bidirectional"))
    )
    (net (code "141") (name "GND") (class "Default")
      (node (ref "C141") (pin "1") (pinfunction "1_1") (pintype "passive"))
      (node (ref "C142") (pin "1") (pinfunction "1_1") (pintype "passive"))
      (node (ref "C143") (pin "1") (pinfunction "1_1") (pintype "passive"))
      (node (ref "C144") (pin "1") (pinfunction "1_1") (pintype "passive"))
      (node (ref "C145") (pin "1") (pinfunction "1_1") (pintype "passive"))
      (node (ref "C146") (pin "1") (pinfunction "1_1") (pintype "passive"))
      (node (ref "D21") (pin "2") (pinfunction "GND_2") (pintype "power_in"))
      (node (ref "D22") (pin "2") (pinfunction "GND_2") (pintype "power_in"))
      (node (ref "D23") (pin "2") (pinfunction "GND_2") (pintype "power_in"))
      (node (ref "D24") (pin "2") (pinfunction "GND_2") (pintype "power_in"))
      (node (ref "D25") (pin "2") (pinfunction "GND_2") (pintype "power_in"))
      (node (ref "D26") (pin "2") (pinfunction "GND_2") (pintype "power_in"))
      (node (ref "D27") (pin "2") (pinfunction "GND_2") (pintype "power_in"))
      (node (ref "D28") (pin "2") (pinfunction "GND_2") (pintype "power_in"))
      (node (ref "D29") (pin "2") (pinfunction "GND_2") (pintype "power_in"))
      (node (ref "D30") (pin "2") (pinfunction "GND_2") (pintype "power_in"))
      (node (ref "D31") (pin "2") (pinfunction "GND_2") (pintype "power_in"))
      (node (ref "D32") (pin "2") (pinfunction "GND_2") (pintype "power_in"))
      (node (ref "D33") (pin "2") (pinfunction "GND_2") (pintype "power_in"))
      (node (ref "D34") (pin "2") (pinfunction "GND_2") (pintype "power_in"))
      (node (ref "D35") (pin "2") (pinfunction "GND_2") (pintype "power_in"))
      (node (ref "D36") (pin "2") (pinfunction "GND_2") (pintype "power_in"))
      (node (ref "D37") (pin "2") (pinfunction "GND_2") (pintype "power_in"))
      (node (ref "D38") (pin "2") (pinfunction "GND_2") (pintype "power_in"))
      (node (ref "D39") (pin "2") (pinfunction "GND_2") (pintype "power_in"))
      (node (ref "D40") (pin "2") (pinfunction "GND_2") (pintype "power_in"))
      (node (ref "D41") (pin "2") (pinfunction "GND_2") (pintype "power_in"))
      (node (ref "D42") (pin "2") (pinfunction "GND_2") (pintype "power_in"))
      (node (ref "D43") (pin "2") (pinfunction "GND_2") (pintype "power_in"))
      (node (ref "D44") (pin "2") (pinfunction "GND_2") (pintype "power_in"))
      (node (ref "D45") (pin "2") (pinfunction "GND_2") (pintype "power_in"))
      (node (ref "D46") (pin "2") (pinfunction "GND_2") (pintype "power_in"))
      (node (ref "D47") (pin "2") (pinfunction "GND_2") (pintype "power_in"))
      (node (ref "D48") (pin "2") (pinfunction "GND_2") (pintype "power_in"))
      (node (ref "D49") (pin "2") (pinfunction "GND_2") (pintype "power_in"))
      (node (ref "D50") (pin "2") (pinfunction "GND_2") (pintype "power_in"))
      (node (ref "D51") (pin "2") (pinfunction "GND_2") (pintype "power_in"))
      (node (ref "D52") (pin "2") (pinfunction "GND_2") (pintype "power_in"))
      (node (ref "D53") (pin "2") (pinfunction "GND_2") (pintype "power_in"))
      (node (ref "J14") (pin "18") (pinfunction "18_18") (pintype "bidirectional"))
      (node (ref "J14") (pin "69") (pinfunction "69_69") (pintype "passive"))
      (node (ref "J14") (pin "70") (pinfunction "70_70") (pintype "passive"))
      (node (ref "J15") (pin "18") (pinfunction "18_18") (pintype "bidirectional"))
      (node (ref "J15") (pin "69") (pinfunction "69_69") (pintype "passive"))
      (node (ref "J15") (pin "70") (pinfunction "70_70") (pintype "passive"))
    )
    (net (code "142") (name "P1V8") (class "Default")
      (node (ref "C141") (pin "2") (pinfunction "2_2") (pintype "passive"))
      (node (ref "C142") (pin "2") (pinfunction "2_2") (pintype "passive"))
      (node (ref "C143") (pin "2") (pinfunction "2_2") (pintype "passive"))
      (node (ref "C144") (pin "2") (pinfunction "2_2") (pintype "passive"))
      (node (ref "C145") (pin "2") (pinfunction "2_2") (pintype "passive"))
      (node (ref "C146") (pin "2") (pinfunction "2_2") (pintype "passive"))
      (node (ref "D21") (pin "5") (pinfunction "VBUS_5") (pintype "power_in"))
      (node (ref "D22") (pin "5") (pinfunction "VBUS_5") (pintype "power_in"))
      (node (ref "D23") (pin "5") (pinfunction "VBUS_5") (pintype "power_in"))
      (node (ref "D24") (pin "5") (pinfunction "VBUS_5") (pintype "power_in"))
      (node (ref "D25") (pin "5") (pinfunction "VBUS_5") (pintype "power_in"))
      (node (ref "D26") (pin "5") (pinfunction "VBUS_5") (pintype "power_in"))
      (node (ref "D27") (pin "5") (pinfunction "VBUS_5") (pintype "power_in"))
      (node (ref "D28") (pin "5") (pinfunction "VBUS_5") (pintype "power_in"))
      (node (ref "D29") (pin "5") (pinfunction "VBUS_5") (pintype "power_in"))
      (node (ref "D30") (pin "5") (pinfunction "VBUS_5") (pintype "power_in"))
      (node (ref "D31") (pin "5") (pinfunction "VBUS_5") (pintype "power_in"))
      (node (ref "D32") (pin "5") (pinfunction "VBUS_5") (pintype "power_in"))
      (node (ref "D33") (pin "5") (pinfunction "VBUS_5") (pintype "power_in"))
      (node (ref "D34") (pin "5") (pinfunction "VBUS_5") (pintype "power_in"))
      (node (ref "D35") (pin "5") (pinfunction "VBUS_5") (pintype "power_in"))
      (node (ref "D36") (pin "5") (pinfunction "VBUS_5") (pintype "power_in"))
      (node (ref "D37") (pin "5") (pinfunction "VBUS_5") (pintype "power_in"))
      (node (ref "D38") (pin "5") (pinfunction "VBUS_5") (pintype "power_in"))
      (node (ref "D39") (pin "5") (pinfunction "VBUS_5") (pintype "power_in"))
      (node (ref "D40") (pin "5") (pinfunction "VBUS_5") (pintype "power_in"))
      (node (ref "D41") (pin "5") (pinfunction "VBUS_5") (pintype "power_in"))
      (node (ref "D42") (pin "5") (pinfunction "VBUS_5") (pintype "power_in"))
      (node (ref "D43") (pin "5") (pinfunction "VBUS_5") (pintype "power_in"))
      (node (ref "D44") (pin "5") (pinfunction "VBUS_5") (pintype "power_in"))
      (node (ref "D45") (pin "5") (pinfunction "VBUS_5") (pintype "power_in"))
      (node (ref "D46") (pin "5") (pinfunction "VBUS_5") (pintype "power_in"))
      (node (ref "D47") (pin "5") (pinfunction "VBUS_5") (pintype "power_in"))
      (node (ref "D48") (pin "5") (pinfunction "VBUS_5") (pintype "power_in"))
      (node (ref "D49") (pin "5") (pinfunction "VBUS_5") (pintype "power_in"))
      (node (ref "D50") (pin "5") (pinfunction "VBUS_5") (pintype "power_in"))
      (node (ref "D51") (pin "5") (pinfunction "VBUS_5") (pintype "power_in"))
      (node (ref "D52") (pin "5") (pinfunction "VBUS_5") (pintype "power_in"))
    )
    (net (code "143") (name "P3V3") (class "Default")
      (node (ref "D53") (pin "5") (pinfunction "VBUS_5") (pintype "power_in"))
      (node (ref "F2") (pin "2") (pinfunction "2_2") (pintype "passive"))
      (node (ref "F3") (pin "2") (pinfunction "2_2") (pintype "passive"))
    )
  )
)
